# 2020.net
KiCad netlist of a schematic drawn in Altium Designer
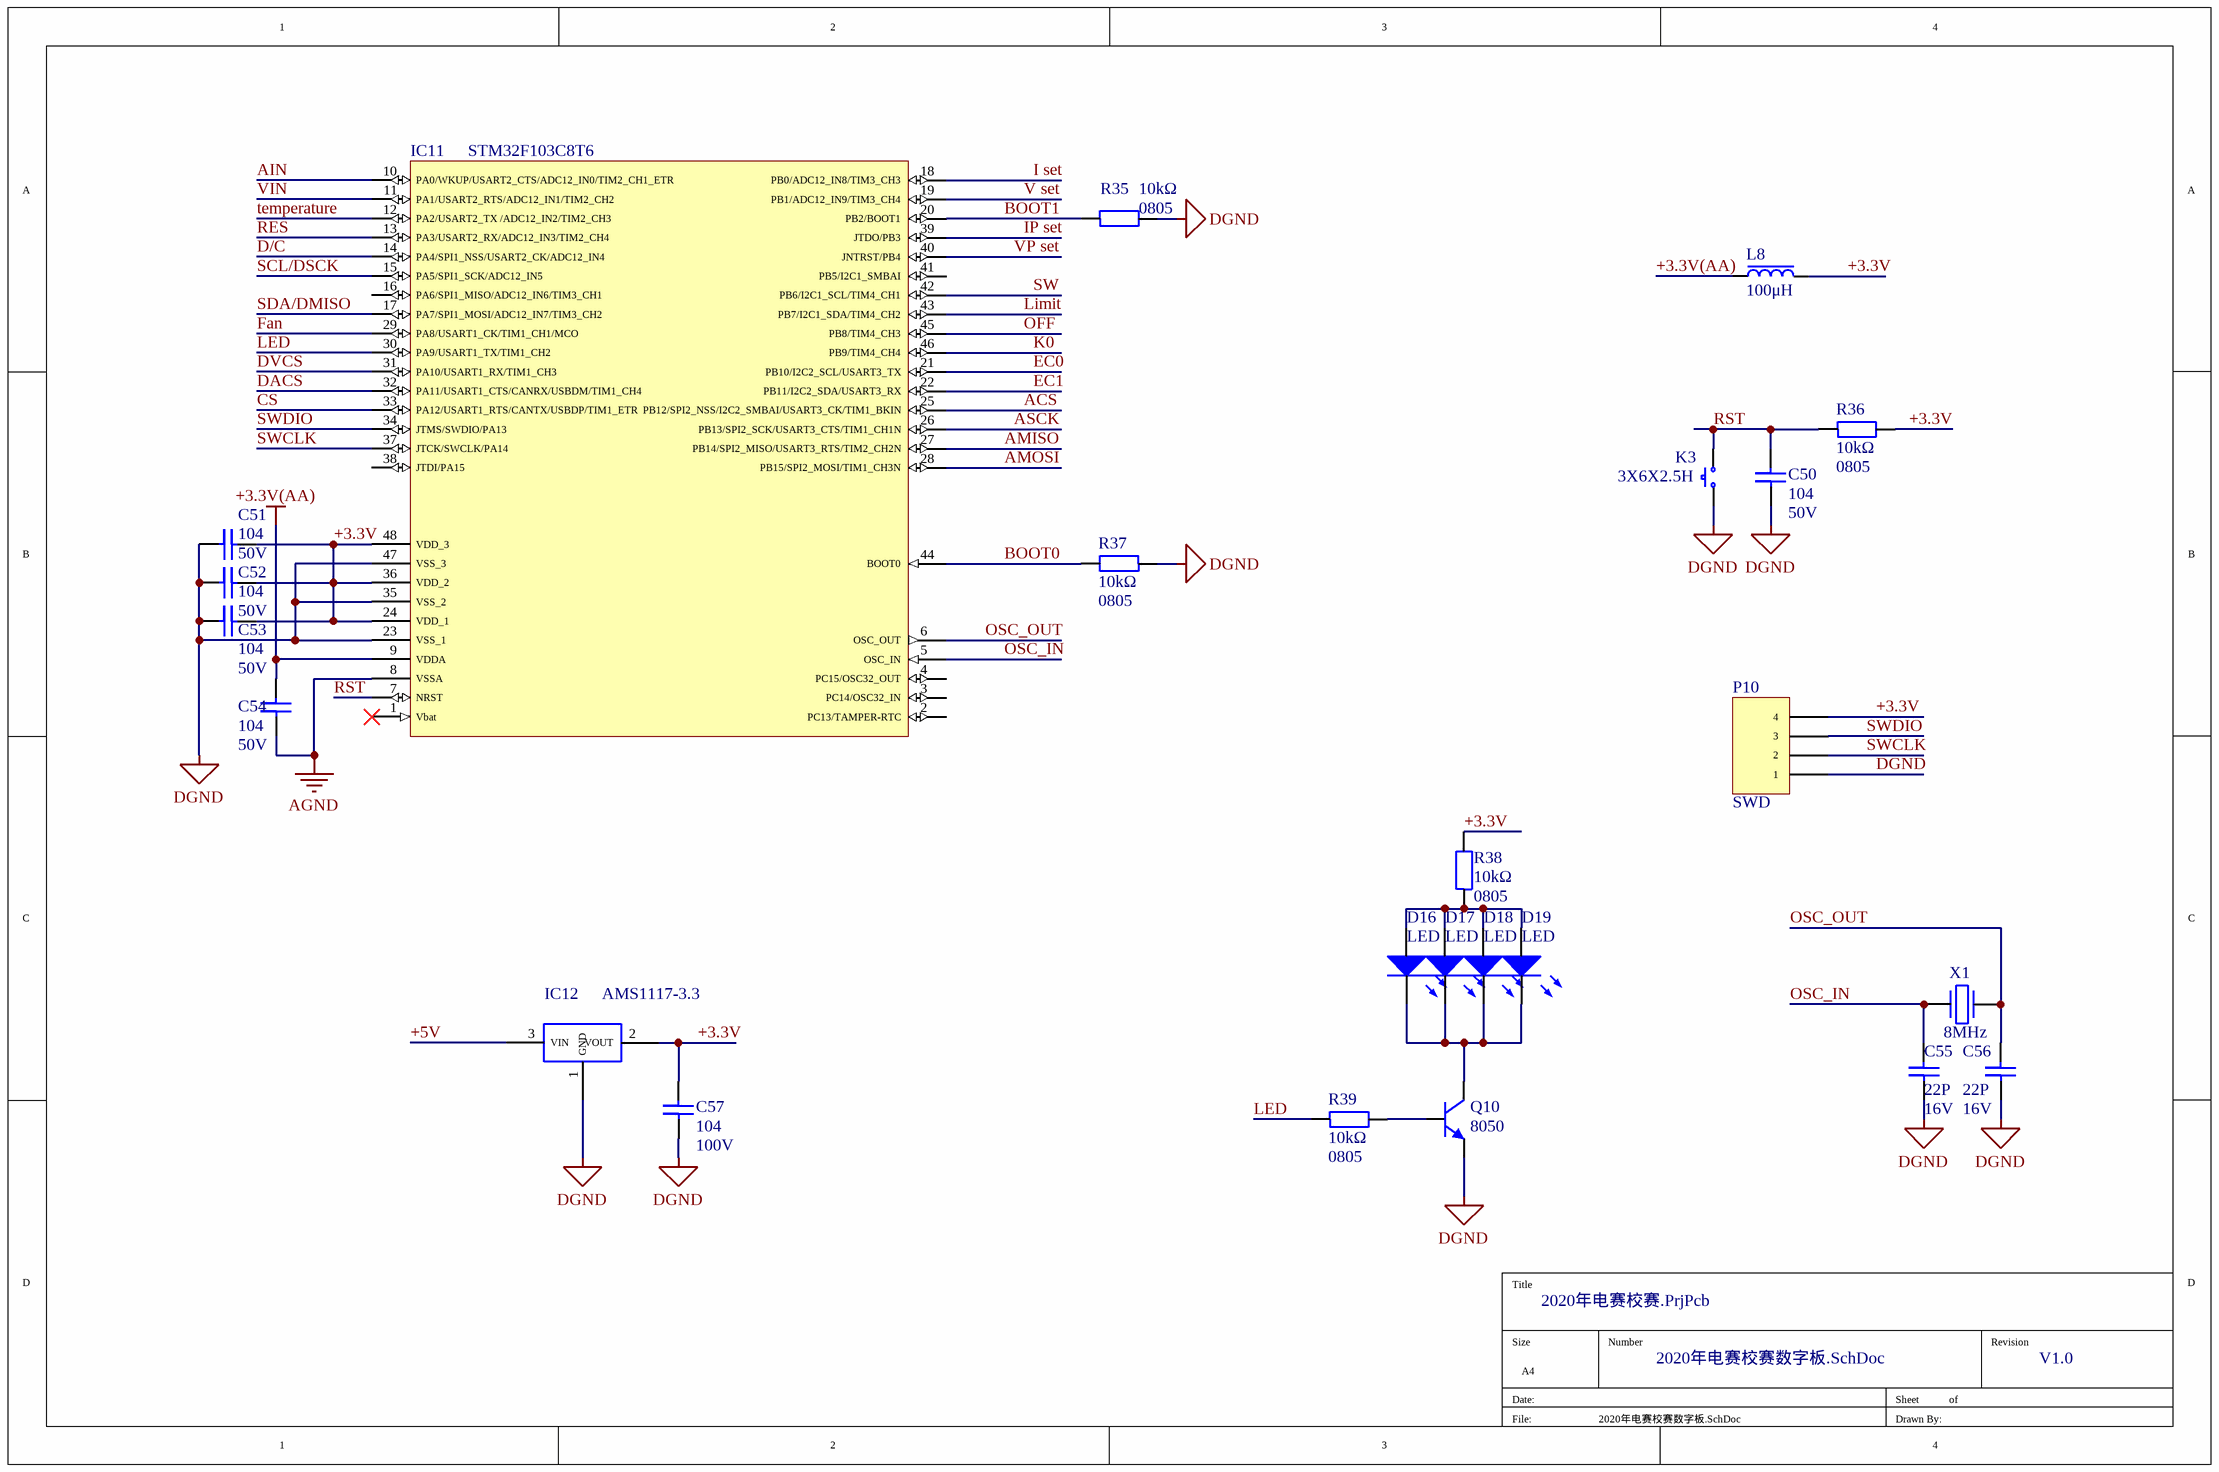
[diagram p0: 2020年电赛校赛数字板.SchDoc]

(export (version "E")
  (design (tool "Eeschema 10.0.6"))
  (components
    (comp (ref "C50")
      (value "104")
      (footprint "C0805")
      (description "无极性电容")
      (fields (field (name "ALTIUM_VALUE") "50V"))
      (libsource (lib "原理图库") (part "104"))
    )
    (comp (ref "C51")
      (value "104")
      (footprint "C0805")
      (description "无极性电容")
      (fields (field (name "ALTIUM_VALUE") "50V"))
      (libsource (lib "原理图库") (part "104"))
    )
    (comp (ref "C52")
      (value "104")
      (footprint "C0805")
      (description "无极性电容")
      (fields (field (name "ALTIUM_VALUE") "50V"))
      (libsource (lib "原理图库") (part "104"))
    )
    (comp (ref "C53")
      (value "104")
      (footprint "C0805")
      (description "无极性电容")
      (fields (field (name "ALTIUM_VALUE") "50V"))
      (libsource (lib "原理图库") (part "104"))
    )
    (comp (ref "C54")
      (value "104")
      (footprint "C0805")
      (description "无极性电容")
      (fields (field (name "ALTIUM_VALUE") "50V"))
      (libsource (lib "原理图库") (part "104"))
    )
    (comp (ref "C55")
      (value "22P")
      (footprint "C0805")
      (description "无极性电容")
      (fields (field (name "ALTIUM_VALUE") "16V"))
      (libsource (lib "原理图库") (part "104"))
    )
    (comp (ref "C56")
      (value "22P")
      (footprint "C0805")
      (description "无极性电容")
      (fields (field (name "ALTIUM_VALUE") "16V"))
      (libsource (lib "原理图库") (part "104"))
    )
    (comp (ref "C57")
      (value "104")
      (footprint "C0805")
      (description "无极性电容")
      (fields (field (name "ALTIUM_VALUE") "100V"))
      (libsource (lib "原理图库") (part "104"))
    )
    (comp (ref "D16") (value "LED") (footprint "LED0805(反贴)") (libsource (lib "原理图库") (part "LED")))
    (comp (ref "D17") (value "LED") (footprint "LED0805(反贴)") (libsource (lib "原理图库") (part "LED")))
    (comp (ref "D18") (value "LED") (footprint "LED0805(反贴)") (libsource (lib "原理图库") (part "LED")))
    (comp (ref "D19") (value "LED") (footprint "LED0805(反贴)") (libsource (lib "原理图库") (part "LED")))
    (comp (ref "IC11")
      (value "STM32F103C8T6")
      (footprint "LQFP-48(0.5MM) - duplicate")
      (description "STM32单片机")
      (libsource (lib "原理图库") (part "STM32F103C8T6"))
    )
    (comp (ref "IC12")
      (value "AMS1117-3.3")
      (footprint "SOT-89")
      (description "LDO")
      (libsource (lib "原理图库") (part "AMS1117-3.3"))
    )
    (comp (ref "K3")
      (value "3X6X2.5H")
      (footprint "3X6X2.5H")
      (description "贴片按键")
      (libsource (lib "原理图库") (part "3X6X2.5H"))
    )
    (comp (ref "L8")
      (value "100μH")
      (footprint "R0805")
      (description "电感")
      (libsource (lib "原理图库") (part "470mH"))
    )
    (comp (ref "P10")
      (value "SWD")
      (footprint "HDR2.54-LI-4P")
      (description "Header, 4-Pin")
      (fields (field (name "PUBLISHER") "Altium Limited"))
      (libsource (lib "Miscellaneous Connectors") (part "Header 4"))
    )
    (comp (ref "Q10")
      (value "8050")
      (footprint "SOT-23")
      (description "三极管")
      (libsource (lib "原理图库") (part "NPN"))
    )
    (comp (ref "R35")
      (value "10kΩ")
      (footprint "R0805")
      (description "贴片/直插电阻")
      (fields (field (name "ALTIUM_VALUE") "0805"))
      (libsource (lib "原理图库") (part "10kΩ"))
    )
    (comp (ref "R36")
      (value "10kΩ")
      (footprint "R0805")
      (description "贴片/直插电阻")
      (fields (field (name "ALTIUM_VALUE") "0805"))
      (libsource (lib "原理图库") (part "10kΩ"))
    )
    (comp (ref "R37")
      (value "10kΩ")
      (footprint "R0805")
      (description "贴片/直插电阻")
      (fields (field (name "ALTIUM_VALUE") "0805"))
      (libsource (lib "原理图库") (part "10kΩ"))
    )
    (comp (ref "R38")
      (value "10kΩ")
      (footprint "R0805")
      (description "贴片/直插电阻")
      (fields (field (name "ALTIUM_VALUE") "0805"))
      (libsource (lib "原理图库") (part "10kΩ"))
    )
    (comp (ref "R39")
      (value "10kΩ")
      (footprint "R0805")
      (description "贴片/直插电阻")
      (fields (field (name "ALTIUM_VALUE") "0805"))
      (libsource (lib "原理图库") (part "10kΩ"))
    )
    (comp (ref "X1")
      (value "8MHz")
      (footprint "Crystal 3225-4P")
      (description "无源晶振")
      (libsource (lib "原理图库") (part "8MHz"))
    )
  )
  (nets
    (net (code "1") (name "+3.3V(AA)") (class "Default")
      (node (ref "C54") (pin "2") (pintype "passive"))
      (node (ref "IC11") (pin "9") (pinfunction "VDDA_9") (pintype "power_in"))
      (node (ref "L8") (pin "2") (pintype "passive"))
    )
    (net (code "2") (name "/+3.3V") (class "Default")
      (node (ref "C51") (pin "2") (pintype "passive"))
      (node (ref "C52") (pin "2") (pintype "passive"))
      (node (ref "C53") (pin "2") (pintype "passive"))
      (node (ref "C57") (pin "2") (pintype "passive"))
      (node (ref "IC11") (pin "24") (pinfunction "VDD_1_24") (pintype "power_in"))
      (node (ref "IC11") (pin "36") (pinfunction "VDD_2_36") (pintype "power_in"))
      (node (ref "IC11") (pin "48") (pinfunction "VDD_3_48") (pintype "power_in"))
      (node (ref "IC12") (pin "2") (pinfunction "VOUT_2") (pintype "power_in"))
      (node (ref "L8") (pin "1") (pintype "passive"))
      (node (ref "P10") (pin "4") (pinfunction "4_4") (pintype "passive"))
      (node (ref "R36") (pin "2") (pintype "passive"))
      (node (ref "R38") (pin "2") (pintype "passive"))
    )
    (net (code "3") (name "/+5V") (class "Default")
      (node (ref "IC12") (pin "3") (pinfunction "VIN_3") (pintype "power_in"))
    )
    (net (code "4") (name "/ACS") (class "Default")
      (node (ref "IC11") (pin "25") (pinfunction "PB12/SPI2_NSS/I2C2_SMBAI/USART3_CK/TIM1_BKIN_25") (pintype "bidirectional"))
    )
    (net (code "5") (name "/AIN") (class "Default")
      (node (ref "IC11") (pin "10") (pinfunction "PA0/WKUP/USART2_CTS/ADC12_IN0/TIM2_CH1_ETR_10") (pintype "bidirectional"))
    )
    (net (code "6") (name "/AMISO") (class "Default")
      (node (ref "IC11") (pin "27") (pinfunction "PB14/SPI2_MISO/USART3_RTS/TIM2_CH2N_27") (pintype "bidirectional"))
    )
    (net (code "7") (name "/AMOSI") (class "Default")
      (node (ref "IC11") (pin "28") (pinfunction "PB15/SPI2_MOSI/TIM1_CH3N_28") (pintype "bidirectional"))
    )
    (net (code "8") (name "/ASCK") (class "Default")
      (node (ref "IC11") (pin "26") (pinfunction "PB13/SPI2_SCK/USART3_CTS/TIM1_CH1N_26") (pintype "bidirectional"))
    )
    (net (code "9") (name "/BOOT0") (class "Default")
      (node (ref "IC11") (pin "44") (pinfunction "BOOT0_44") (pintype "input"))
      (node (ref "R37") (pin "2") (pintype "passive"))
    )
    (net (code "10") (name "/BOOT1") (class "Default")
      (node (ref "IC11") (pin "20") (pinfunction "PB2/BOOT1_20") (pintype "bidirectional"))
      (node (ref "R35") (pin "1") (pintype "passive"))
    )
    (net (code "11") (name "/CS") (class "Default")
      (node (ref "IC11") (pin "33") (pinfunction "PA12/USART1_RTS/CANTX/USBDP/TIM1_ETR_33") (pintype "bidirectional"))
    )
    (net (code "12") (name "/DACS") (class "Default")
      (node (ref "IC11") (pin "32") (pinfunction "PA11/USART1_CTS/CANRX/USBDM/TIM1_CH4_32") (pintype "bidirectional"))
    )
    (net (code "13") (name "/DVCS") (class "Default")
      (node (ref "IC11") (pin "31") (pinfunction "PA10/USART1_RX/TIM1_CH3_31") (pintype "bidirectional"))
    )
    (net (code "14") (name "/D{slash}C") (class "Default")
      (node (ref "IC11") (pin "14") (pinfunction "PA4/SPI1_NSS/USART2_CK/ADC12_IN4_14") (pintype "bidirectional"))
    )
    (net (code "15") (name "/EC0") (class "Default")
      (node (ref "IC11") (pin "21") (pinfunction "PB10/I2C2_SCL/USART3_TX_21") (pintype "bidirectional"))
    )
    (net (code "16") (name "/EC1") (class "Default")
      (node (ref "IC11") (pin "22") (pinfunction "PB11/I2C2_SDA/USART3_RX_22") (pintype "bidirectional"))
    )
    (net (code "17") (name "/Fan") (class "Default")
      (node (ref "IC11") (pin "29") (pinfunction "PA8/USART1_CK/TIM1_CH1/MCO_29") (pintype "bidirectional"))
    )
    (net (code "18") (name "/I set") (class "Default")
      (node (ref "IC11") (pin "18") (pinfunction "PB0/ADC12_IN8/TIM3_CH3_18") (pintype "bidirectional"))
    )
    (net (code "19") (name "/IP set") (class "Default")
      (node (ref "IC11") (pin "39") (pinfunction "JTDO/PB3_39") (pintype "bidirectional"))
    )
    (net (code "20") (name "/K0") (class "Default")
      (node (ref "IC11") (pin "46") (pinfunction "PB9/TIM4_CH4_46") (pintype "bidirectional"))
    )
    (net (code "21") (name "/LED") (class "Default")
      (node (ref "IC11") (pin "30") (pinfunction "PA9/USART1_TX/TIM1_CH2_30") (pintype "bidirectional"))
      (node (ref "R39") (pin "1") (pintype "passive"))
    )
    (net (code "22") (name "/Limit") (class "Default")
      (node (ref "IC11") (pin "43") (pinfunction "PB7/I2C1_SDA/TIM4_CH2_43") (pintype "bidirectional"))
    )
    (net (code "23") (name "/OFF") (class "Default")
      (node (ref "IC11") (pin "45") (pinfunction "PB8/TIM4_CH3_45") (pintype "bidirectional"))
    )
    (net (code "24") (name "/OSC_IN") (class "Default")
      (node (ref "C55") (pin "2") (pintype "passive"))
      (node (ref "IC11") (pin "5") (pinfunction "OSC_IN_5") (pintype "input"))
      (node (ref "X1") (pin "2") (pintype "passive"))
    )
    (net (code "25") (name "/OSC_OUT") (class "Default")
      (node (ref "C56") (pin "2") (pintype "passive"))
      (node (ref "IC11") (pin "6") (pinfunction "OSC_OUT_6") (pintype "output"))
      (node (ref "X1") (pin "1") (pintype "passive"))
    )
    (net (code "26") (name "/RES") (class "Default")
      (node (ref "IC11") (pin "13") (pinfunction "PA3/USART2_RX/ADC12_IN3/TIM2_CH4_13") (pintype "bidirectional"))
    )
    (net (code "27") (name "/RST") (class "Default")
      (node (ref "C50") (pin "2") (pintype "passive"))
      (node (ref "IC11") (pin "7") (pinfunction "NRST_7") (pintype "bidirectional"))
      (node (ref "K3") (pin "2") (pintype "passive"))
      (node (ref "R36") (pin "1") (pintype "passive"))
    )
    (net (code "28") (name "/SCL{slash}DSCK") (class "Default")
      (node (ref "IC11") (pin "15") (pinfunction "PA5/SPI1_SCK/ADC12_IN5_15") (pintype "bidirectional"))
    )
    (net (code "29") (name "/SDA{slash}DMISO") (class "Default")
      (node (ref "IC11") (pin "17") (pinfunction "PA7/SPI1_MOSI/ADC12_IN7/TIM3_CH2_17") (pintype "bidirectional"))
    )
    (net (code "30") (name "/SW") (class "Default")
      (node (ref "IC11") (pin "42") (pinfunction "PB6/I2C1_SCL/TIM4_CH1_42") (pintype "bidirectional"))
    )
    (net (code "31") (name "/SWCLK") (class "Default")
      (node (ref "IC11") (pin "37") (pinfunction "JTCK/SWCLK/PA14_37") (pintype "bidirectional"))
      (node (ref "P10") (pin "2") (pinfunction "2_2") (pintype "passive"))
    )
    (net (code "32") (name "/SWDIO") (class "Default")
      (node (ref "IC11") (pin "34") (pinfunction "JTMS/SWDIO/PA13_34") (pintype "bidirectional"))
      (node (ref "P10") (pin "3") (pinfunction "3_3") (pintype "passive"))
    )
    (net (code "33") (name "/V set") (class "Default")
      (node (ref "IC11") (pin "19") (pinfunction "PB1/ADC12_IN9/TIM3_CH4_19") (pintype "bidirectional"))
    )
    (net (code "34") (name "/VIN") (class "Default")
      (node (ref "IC11") (pin "11") (pinfunction "PA1/USART2_RTS/ADC12_IN1/TIM2_CH2_11") (pintype "bidirectional"))
    )
    (net (code "35") (name "/VP set") (class "Default")
      (node (ref "IC11") (pin "40") (pinfunction "JNTRST/PB4_40") (pintype "bidirectional"))
    )
    (net (code "36") (name "/temperature") (class "Default")
      (node (ref "IC11") (pin "12") (pinfunction "PA2/USART2_TX_/ADC12_IN2/TIM2_CH3_12") (pintype "bidirectional"))
    )
    (net (code "37") (name "AGND") (class "Default")
      (node (ref "C54") (pin "1") (pintype "passive"))
      (node (ref "IC11") (pin "8") (pinfunction "VSSA_8") (pintype "power_in"))
    )
    (net (code "38") (name "DGND") (class "Default")
      (node (ref "C50") (pin "1") (pintype "passive"))
      (node (ref "C51") (pin "1") (pintype "passive"))
      (node (ref "C52") (pin "1") (pintype "passive"))
      (node (ref "C53") (pin "1") (pintype "passive"))
      (node (ref "C55") (pin "1") (pintype "passive"))
      (node (ref "C56") (pin "1") (pintype "passive"))
      (node (ref "C57") (pin "1") (pintype "passive"))
      (node (ref "IC11") (pin "23") (pinfunction "VSS_1_23") (pintype "power_in"))
      (node (ref "IC11") (pin "35") (pinfunction "VSS_2_35") (pintype "power_in"))
      (node (ref "IC11") (pin "47") (pinfunction "VSS_3_47") (pintype "power_in"))
      (node (ref "IC12") (pin "1") (pinfunction "GND_1") (pintype "passive"))
      (node (ref "K3") (pin "1") (pintype "passive"))
      (node (ref "P10") (pin "1") (pinfunction "1_1") (pintype "passive"))
      (node (ref "Q10") (pin "2") (pinfunction "E_2") (pintype "passive"))
      (node (ref "R35") (pin "2") (pintype "passive"))
      (node (ref "R37") (pin "1") (pintype "passive"))
    )
    (net (code "39") (name "Net-(D16-A)") (class "Default")
      (node (ref "D16") (pin "1") (pinfunction "A_1") (pintype "passive"))
      (node (ref "D17") (pin "1") (pinfunction "A_1") (pintype "passive"))
      (node (ref "D18") (pin "1") (pinfunction "A_1") (pintype "passive"))
      (node (ref "D19") (pin "1") (pinfunction "A_1") (pintype "passive"))
      (node (ref "R38") (pin "1") (pintype "passive"))
    )
    (net (code "40") (name "Net-(D16-K)") (class "Default")
      (node (ref "D16") (pin "2") (pinfunction "K_2") (pintype "passive"))
      (node (ref "D17") (pin "2") (pinfunction "K_2") (pintype "passive"))
      (node (ref "D18") (pin "2") (pinfunction "K_2") (pintype "passive"))
      (node (ref "D19") (pin "2") (pinfunction "K_2") (pintype "passive"))
      (node (ref "Q10") (pin "3") (pinfunction "C_3") (pintype "passive"))
    )
    (net (code "41") (name "Net-(Q10-B)") (class "Default")
      (node (ref "Q10") (pin "1") (pinfunction "B_1") (pintype "passive"))
      (node (ref "R39") (pin "2") (pintype "passive"))
    )
    (net (code "42") (name "unconnected-(IC11-JTDI{slash}PA15-Pad38)") (class "Default")
      (node (ref "IC11") (pin "38") (pinfunction "JTDI/PA15_38") (pintype "bidirectional"))
    )
    (net (code "43") (name "unconnected-(IC11-PA6{slash}SPI1_MISO{slash}ADC12_IN6{slash}TIM3_CH1-Pad16)") (class "Default")
      (node (ref "IC11") (pin "16") (pinfunction "PA6/SPI1_MISO/ADC12_IN6/TIM3_CH1_16") (pintype "bidirectional"))
    )
    (net (code "44") (name "unconnected-(IC11-PB5{slash}I2C1_SMBAI-Pad41)") (class "Default")
      (node (ref "IC11") (pin "41") (pinfunction "PB5/I2C1_SMBAI_41") (pintype "bidirectional"))
    )
    (net (code "45") (name "unconnected-(IC11-PC13{slash}TAMPER-RTC-Pad2)") (class "Default")
      (node (ref "IC11") (pin "2") (pinfunction "PC13/TAMPER-RTC_2") (pintype "bidirectional"))
    )
    (net (code "46") (name "unconnected-(IC11-PC14{slash}OSC32_IN-Pad3)") (class "Default")
      (node (ref "IC11") (pin "3") (pinfunction "PC14/OSC32_IN_3") (pintype "bidirectional"))
    )
    (net (code "47") (name "unconnected-(IC11-PC15{slash}OSC32_OUT-Pad4)") (class "Default")
      (node (ref "IC11") (pin "4") (pinfunction "PC15/OSC32_OUT_4") (pintype "bidirectional"))
    )
    (net (code "48") (name "unconnected-(IC11-Vbat-Pad1)") (class "Default")
      (node (ref "IC11") (pin "1") (pinfunction "Vbat_1") (pintype "input+no_connect"))
    )
  )
)
